# 00_POWER.net
KiCad netlist of a schematic drawn in Altium Designer
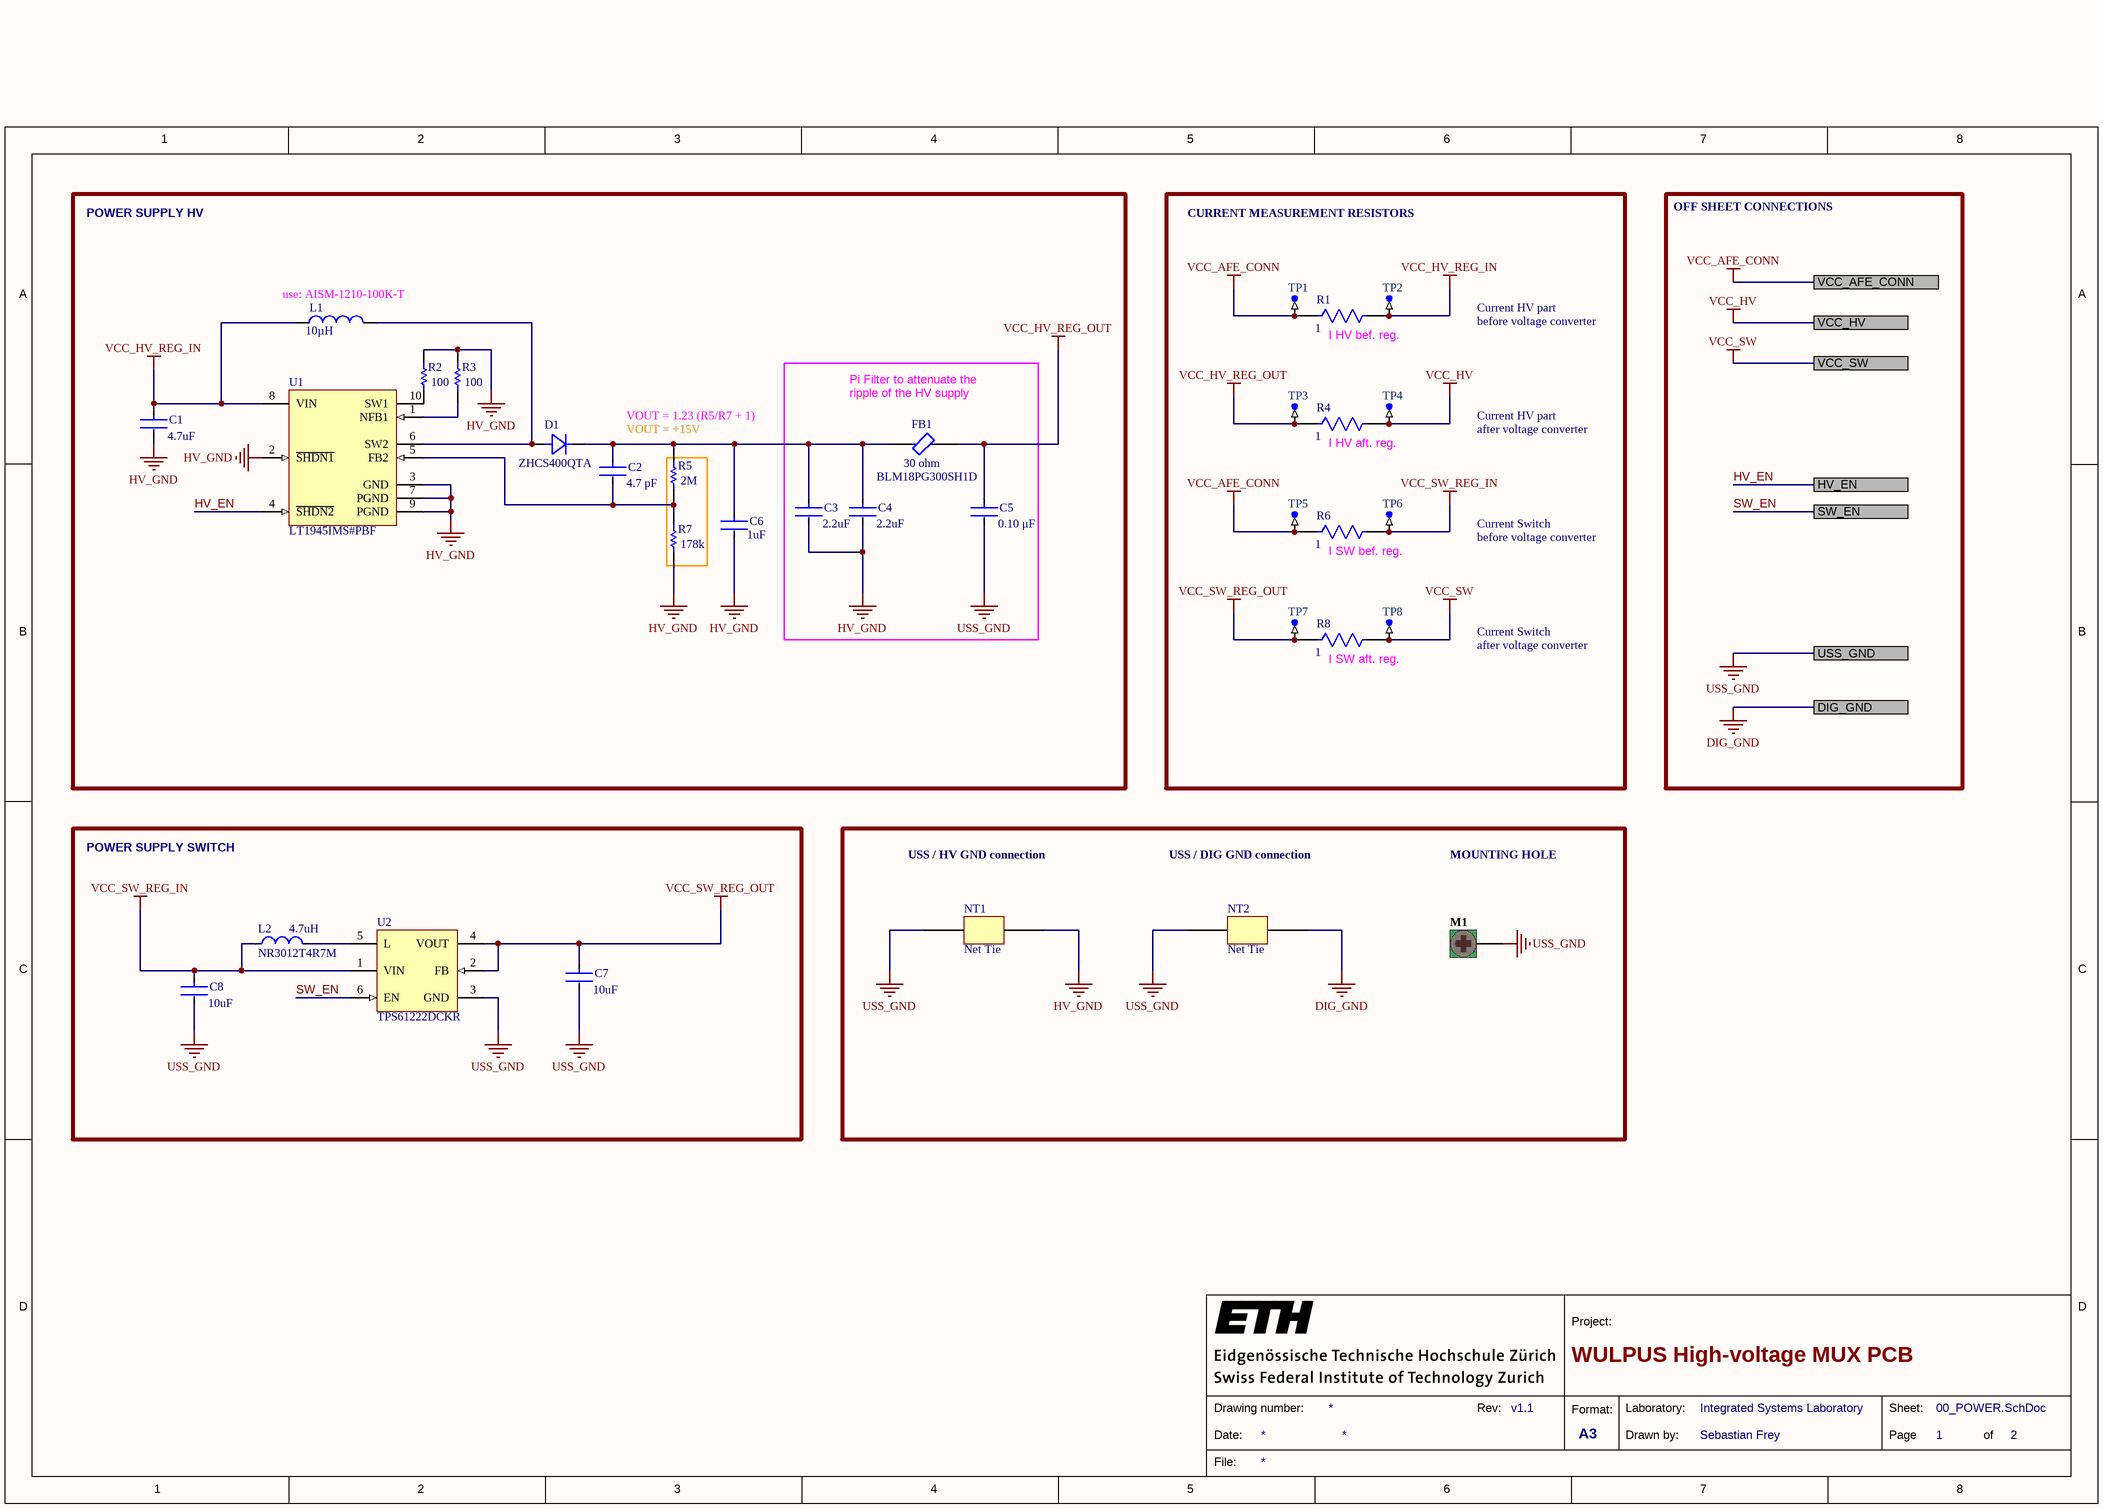
[diagram p0: 00_POWER.SchDoc]

(export (version "E")
  (design (tool "Eeschema 10.0.6"))
  (components
    (comp (ref "C1")
      (value "06036D475KAT2A")
      (footprint "FP-0603-L_1_6_0_15-W_0_81-MFG")
      (description "General Purpose Ceramic Capacitor, 0603, 4.7uF, 10%, X5R, 15%, 6.3V")
      (fields
        (field (name "VOLTAGE") "6.3V")
        (field (name "TOLERANCE") "20%")
        (field (name "CAPACITANCE") "4.7uF")
      )
      (libsource (lib "Altium Content Vault") (part "02cd4be3c70576c341d710602a673aa"))
    )
    (comp (ref "C2")
      (value "C0402C479C5GACTU")
      (footprint "FP-C0402-BB-MFG")
      (description "CAP CER 4.7PF 50V NP0 0402")
      (fields
        (field (name "TOLERANCE") "0.25 pF")
        (field (name "OCTOPART") "https://octopart.com/c0402c479c5gactu-kemet-9144199")
        (field (name "CAPACITANCE") "4.7 pF")
      )
      (libsource (lib "Altium Content Vault") (part "b4654b650e69147ec39a6b967a45e02"))
    )
    (comp (ref "C3")
      (value "GRM188R61H225KE11D")
      (footprint "FP-GRM188-0_2-IPC_C")
      (description "Chip Multilayer Ceramic Capacitors for General Purpose, 0603, 2.2uF, X5R, 15%, 10%, 50V")
      (fields (field (name "TOLERANCE") "10%") (field (name "CAPACITANCE") "2.2uF"))
      (libsource (lib "Altium Content Vault") (part "11868f565c42a9108669ba33697ecf6"))
    )
    (comp (ref "C4")
      (value "GRM188R61H225KE11D")
      (footprint "FP-GRM188-0_2-IPC_C")
      (description "Chip Multilayer Ceramic Capacitors for General Purpose, 0603, 2.2uF, X5R, 15%, 10%, 50V")
      (fields (field (name "TOLERANCE") "10%") (field (name "CAPACITANCE") "2.2uF"))
      (libsource (lib "Altium Content Vault") (part "11868f565c42a9108669ba33697ecf6"))
    )
    (comp (ref "C5")
      (value "0.10 μF")
      (footprint "FP-C0603C-CF-MFG")
      (description "CAP CER 0.1UF 50V 20% X7R 0603")
      (fields
        (field (name "MANUFACTURER PART NUMBER") "C0603C104M5RACTU")
        (field (name "MANUFACTURER") "KEMET")
      )
      (libsource (lib "Altium Content Vault") (part "b4654b650e69147ec39a6b967a45e02"))
    )
    (comp (ref "C6")
      (value "GMK316BJ105KLHT")
      (footprint "FP-1206-L_3_2_0_15-W_1_6-IPC_B")
      (description "None")
      (fields (field (name "CAPACITANCE") "1uF") (field (name "TOLERANCE") "10%"))
      (libsource (lib "Altium Content Vault") (part "02cd4be3c70576c341d710602a673aa"))
    )
    (comp (ref "C7")
      (value "GRM188R60J106ME47D")
      (footprint "FP-GRM188-0_1-e0_2_0_55-IPC_A")
      (description "Chip Multilayer Ceramic Capacitors for General Purpose, 0603, 10uF, X5R, 15%, 20%, 6.3V")
      (fields
        (field (name "CAPACITANCE") "10uF")
        (field (name "VOLTAGE") "6.3V")
        (field (name "TOLERANCE") "20%")
      )
      (libsource (lib "Altium Content Vault") (part "02cd4be3c70576c341d710602a673aa"))
    )
    (comp (ref "C8")
      (value "GRM188R60J106ME47D")
      (footprint "FP-GRM188-0_1-e0_2_0_55-IPC_A")
      (description "Chip Multilayer Ceramic Capacitors for General Purpose, 0603, 10uF, X5R, 15%, 20%, 6.3V")
      (fields
        (field (name "CAPACITANCE") "10uF")
        (field (name "VOLTAGE") "6.3V")
        (field (name "TOLERANCE") "20%")
      )
      (libsource (lib "Altium Content Vault") (part "02cd4be3c70576c341d710602a673aa"))
    )
    (comp (ref "D1")
      (value "ZHCS400QTA")
      (footprint "PcbLib1:DIODE_SOD323_DIO")
      (description "Diode Schottky 40V 1A Automotive 2-Pin SOD-323 T/R")
      (fields (field (name "MANUFACTURER") "Diodes"))
      (libsource (lib "Schlib1") (part "ZHCS400QTA"))
    )
    (comp (ref "FB1")
      (value "BLM18PG300SH1D")
      (footprint "FP-BLM18-0_15-t0_8-IPC_A")
      (description "Chip Ferrite Bead, 0603, 30Ω @ 100MHz, 0.05Ω, , 1A")
      (fields (field (name "IMPEDANCE") "30 ohm") (field (name "TOLERANCE") "25%"))
      (libsource (lib "Altium Content Vault") (part "5f30dd21d616792df468990f7003faa"))
    )
    (comp (ref "L1")
      (value "B82422A1103K100")
      (footprint "TDK-B82422A1103K100_V")
      (description "Wirewound Inductor, 10 uF, +/- 10%, 180 mA, -55 to 125 degC, 2-Pin SMD, RoHS, Tape and Reel")
      (fields
        (field (name "INDUCTANCE") "10µH")
        (field (name "TOLERANCE") "±10%")
        (field (name "MANUFACTURER") "EPCOS-(TDK)")
      )
      (libsource (lib "Altium Content Vault") (part "IND-2"))
    )
    (comp (ref "L2")
      (value "NR3012T4R7M")
      (footprint "FP-NR3012-MFG")
      (description "SMD Power Inductors 4.7uH ±20% 0.77A 0.13Ω")
      (fields (field (name "TOLERANCE") "20%") (field (name "INDUCTANCE") "4.7uH"))
      (libsource (lib "Altium Content Vault") (part "725321dda6339637d4d059423bc1c3c"))
    )
    (comp (ref "M1")
      (value "Mounting Hole for AFE PCB")
      (footprint "Hole M2")
      (description "M2 Hole, 2.4mm drill, 5mm landing pads, 3mm pad in middle layers, no overlay")
      (libsource (lib "ETHZ Vault") (part "Hole"))
    )
    (comp (ref "NT1")
      (value "Net Tie")
      (footprint "PcbLib1:Net_Tie_Top_Bottom")
      (libsource (lib "Schlib1") (part "Net_Tie"))
    )
    (comp (ref "NT2")
      (value "Net Tie")
      (footprint "PcbLib1:Net_Tie_Top_Bottom")
      (libsource (lib "Schlib1") (part "Net_Tie"))
    )
    (comp (ref "R1")
      (value "CSR0402FK1R00")
      (footprint "FP-CSR0402-MFG")
      (description "RES 1 OHM 1% 1/8W 0402")
      (fields (field (name "TOLERANCE") "1%") (field (name "RESISTANCE") "1"))
      (libsource (lib "Altium Content Vault") (part "1029c3af85768c4190bb7ad29bc67b5"))
    )
    (comp (ref "R2")
      (value "ERJ-2GEJ101X")
      (footprint "RESC1005X40X25NL05T05")
      (fields (field (name "MANUFACTURER") "Panasonic") (field (name "RESISTANCE") "100"))
      (libsource (lib "Altium Content Vault") (part "RES"))
    )
    (comp (ref "R3")
      (value "ERJ-2GEJ101X")
      (footprint "RESC1005X40X25NL05T05")
      (fields (field (name "MANUFACTURER") "Panasonic") (field (name "RESISTANCE") "100"))
      (libsource (lib "Altium Content Vault") (part "RES"))
    )
    (comp (ref "R4")
      (value "CSR0402FK1R00")
      (footprint "FP-CSR0402-MFG")
      (description "RES 1 OHM 1% 1/8W 0402")
      (fields (field (name "TOLERANCE") "1%") (field (name "RESISTANCE") "1"))
      (libsource (lib "Altium Content Vault") (part "1029c3af85768c4190bb7ad29bc67b5"))
    )
    (comp (ref "R5")
      (value "RC0402FR-072ML")
      (footprint "RESC1005X40X25NL05T10")
      (fields (field (name "MANUFACTURER") "Yageo / Phycomp") (field (name "RESISTANCE") "2M"))
      (libsource (lib "Altium Content Vault") (part "RES"))
    )
    (comp (ref "R6")
      (value "CSR0402FK1R00")
      (footprint "FP-CSR0402-MFG")
      (description "RES 1 OHM 1% 1/8W 0402")
      (fields (field (name "TOLERANCE") "1%") (field (name "RESISTANCE") "1"))
      (libsource (lib "Altium Content Vault") (part "1029c3af85768c4190bb7ad29bc67b5"))
    )
    (comp (ref "R7")
      (value "ERJ-2RKF1783X")
      (footprint "RESC1005X40X25ML05T05")
      (fields (field (name "MANUFACTURER") "Panasonic") (field (name "RESISTANCE") "178k"))
      (libsource (lib "Altium Content Vault") (part "RES"))
    )
    (comp (ref "R8")
      (value "CSR0402FK1R00")
      (footprint "FP-CSR0402-MFG")
      (description "RES 1 OHM 1% 1/8W 0402")
      (fields (field (name "TOLERANCE") "1%") (field (name "RESISTANCE") "1"))
      (libsource (lib "Altium Content Vault") (part "1029c3af85768c4190bb7ad29bc67b5"))
    )
    (comp (ref "TP1")
      (value "TP-SM-C-100")
      (footprint "TP-SM-C-100")
      (description "Test Point, Surface Mount, Circular, Pad Diameter 1 mm")
      (libsource (lib "Altium Content Vault") (part "TP-SM"))
    )
    (comp (ref "TP2")
      (value "TP-SM-C-100")
      (footprint "TP-SM-C-100")
      (description "Test Point, Surface Mount, Circular, Pad Diameter 1 mm")
      (libsource (lib "Altium Content Vault") (part "TP-SM"))
    )
    (comp (ref "TP3")
      (value "TP-SM-C-100")
      (footprint "TP-SM-C-100")
      (description "Test Point, Surface Mount, Circular, Pad Diameter 1 mm")
      (libsource (lib "Altium Content Vault") (part "TP-SM"))
    )
    (comp (ref "TP4")
      (value "TP-SM-C-100")
      (footprint "TP-SM-C-100")
      (description "Test Point, Surface Mount, Circular, Pad Diameter 1 mm")
      (libsource (lib "Altium Content Vault") (part "TP-SM"))
    )
    (comp (ref "TP5")
      (value "TP-SM-C-100")
      (footprint "TP-SM-C-100")
      (description "Test Point, Surface Mount, Circular, Pad Diameter 1 mm")
      (libsource (lib "Altium Content Vault") (part "TP-SM"))
    )
    (comp (ref "TP6")
      (value "TP-SM-C-100")
      (footprint "TP-SM-C-100")
      (description "Test Point, Surface Mount, Circular, Pad Diameter 1 mm")
      (libsource (lib "Altium Content Vault") (part "TP-SM"))
    )
    (comp (ref "TP7")
      (value "TP-SM-C-100")
      (footprint "TP-SM-C-100")
      (description "Test Point, Surface Mount, Circular, Pad Diameter 1 mm")
      (libsource (lib "Altium Content Vault") (part "TP-SM"))
    )
    (comp (ref "TP8")
      (value "TP-SM-C-100")
      (footprint "TP-SM-C-100")
      (description "Test Point, Surface Mount, Circular, Pad Diameter 1 mm")
      (libsource (lib "Altium Content Vault") (part "TP-SM"))
    )
    (comp (ref "U1")
      (value "LT1945IMS#PBF")
      (footprint "LT-MS-10_L")
      (fields (field (name "MANUFACTURER") "Linear Technology"))
      (libsource (lib "Altium Content Vault") (part "LT-LT1945-MS-10"))
    )
    (comp (ref "U2")
      (value "TPS61222DCKR")
      (footprint "DCK0006A_L")
      (fields (field (name "MANUFACTURER") "Texas Instruments"))
      (libsource (lib "Altium Content Vault") (part "TI-TPS61222DCK6"))
    )
  )
  (nets
    (net (code "1") (name "/HV_EN") (class "Default")
      (node (ref "U1") (pin "4") (pinfunction "~{SHDN2}_4") (pintype "input"))
    )
    (net (code "2") (name "/SW_EN") (class "Default")
      (node (ref "U2") (pin "6") (pinfunction "EN_6") (pintype "input"))
    )
    (net (code "3") (name "DIG_GND") (class "Default")
      (node (ref "NT2") (pin "2") (pinfunction "2_2") (pintype "passive"))
    )
    (net (code "4") (name "HV_GND") (class "Default")
      (node (ref "C1") (pin "2") (pinfunction "2_2") (pintype "passive"))
      (node (ref "C3") (pin "2") (pinfunction "2_2") (pintype "passive"))
      (node (ref "C4") (pin "2") (pinfunction "2_2") (pintype "passive"))
      (node (ref "C6") (pin "2") (pinfunction "2_2") (pintype "passive"))
      (node (ref "NT1") (pin "2") (pinfunction "2_2") (pintype "passive"))
      (node (ref "R2") (pin "2") (pinfunction "2_2") (pintype "passive"))
      (node (ref "R3") (pin "2") (pinfunction "2_2") (pintype "passive"))
      (node (ref "R7") (pin "1") (pinfunction "1_1") (pintype "passive"))
      (node (ref "U1") (pin "2") (pinfunction "~{SHDN1}_2") (pintype "input"))
      (node (ref "U1") (pin "3") (pinfunction "GND_3") (pintype "power_in"))
      (node (ref "U1") (pin "7") (pinfunction "PGND_7") (pintype "power_in"))
      (node (ref "U1") (pin "9") (pinfunction "PGND_9") (pintype "power_in"))
    )
    (net (code "5") (name "Net-(C2-Pad1)") (class "Default")
      (node (ref "C2") (pin "1") (pinfunction "1_1") (pintype "passive"))
      (node (ref "C3") (pin "1") (pinfunction "1_1") (pintype "passive"))
      (node (ref "C4") (pin "1") (pinfunction "1_1") (pintype "passive"))
      (node (ref "C6") (pin "1") (pinfunction "1_1") (pintype "passive"))
      (node (ref "D1") (pin "1") (pinfunction "1_1") (pintype "passive"))
      (node (ref "FB1") (pin "1") (pinfunction "1_1") (pintype "passive"))
      (node (ref "R5") (pin "2") (pinfunction "2_2") (pintype "passive"))
    )
    (net (code "6") (name "Net-(U1-FB2)") (class "Default")
      (node (ref "C2") (pin "2") (pinfunction "2_2") (pintype "passive"))
      (node (ref "R5") (pin "1") (pinfunction "1_1") (pintype "passive"))
      (node (ref "R7") (pin "2") (pinfunction "2_2") (pintype "passive"))
      (node (ref "U1") (pin "5") (pinfunction "FB2_5") (pintype "input"))
    )
    (net (code "7") (name "Net-(U1-NFB1)") (class "Default")
      (node (ref "R3") (pin "1") (pinfunction "1_1") (pintype "passive"))
      (node (ref "U1") (pin "1") (pinfunction "NFB1_1") (pintype "input"))
    )
    (net (code "8") (name "Net-(U1-SW1)") (class "Default")
      (node (ref "R2") (pin "1") (pinfunction "1_1") (pintype "passive"))
      (node (ref "U1") (pin "10") (pinfunction "SW1_10") (pintype "power_in"))
    )
    (net (code "9") (name "Net-(U1-SW2)") (class "Default")
      (node (ref "D1") (pin "2") (pinfunction "2_2") (pintype "passive"))
      (node (ref "L1") (pin "2") (pinfunction "2_2") (pintype "passive"))
      (node (ref "U1") (pin "6") (pinfunction "SW2_6") (pintype "power_in"))
    )
    (net (code "10") (name "Net-(U2-L)") (class "Default")
      (node (ref "L2") (pin "2") (pinfunction "2_2") (pintype "passive"))
      (node (ref "U2") (pin "5") (pinfunction "L_5") (pintype "power_in"))
    )
    (net (code "11") (name "USS_GND") (class "Default")
      (node (ref "C5") (pin "2") (pinfunction "2_2") (pintype "passive"))
      (node (ref "C7") (pin "2") (pinfunction "2_2") (pintype "passive"))
      (node (ref "C8") (pin "2") (pinfunction "2_2") (pintype "passive"))
      (node (ref "M1") (pin "1") (pinfunction "1_1") (pintype "passive"))
      (node (ref "NT1") (pin "1") (pinfunction "1_1") (pintype "passive"))
      (node (ref "NT2") (pin "1") (pinfunction "1_1") (pintype "passive"))
      (node (ref "U2") (pin "3") (pinfunction "GND_3") (pintype "power_in"))
    )
    (net (code "12") (name "VCC_AFE_CONN") (class "Default")
      (node (ref "R1") (pin "1") (pinfunction "1_1") (pintype "passive"))
      (node (ref "R6") (pin "1") (pinfunction "1_1") (pintype "passive"))
      (node (ref "TP1") (pin "1") (pinfunction "1_1") (pintype "input"))
      (node (ref "TP5") (pin "1") (pinfunction "1_1") (pintype "input"))
    )
    (net (code "13") (name "VCC_HV") (class "Default")
      (node (ref "R4") (pin "2") (pinfunction "2_2") (pintype "passive"))
      (node (ref "TP4") (pin "1") (pinfunction "1_1") (pintype "input"))
    )
    (net (code "14") (name "VCC_HV_REG_IN") (class "Default")
      (node (ref "C1") (pin "1") (pinfunction "1_1") (pintype "passive"))
      (node (ref "L1") (pin "1") (pinfunction "1_1") (pintype "passive"))
      (node (ref "R1") (pin "2") (pinfunction "2_2") (pintype "passive"))
      (node (ref "TP2") (pin "1") (pinfunction "1_1") (pintype "input"))
      (node (ref "U1") (pin "8") (pinfunction "VIN_8") (pintype "power_in"))
    )
    (net (code "15") (name "VCC_HV_REG_OUT") (class "Default")
      (node (ref "C5") (pin "1") (pinfunction "1_1") (pintype "passive"))
      (node (ref "FB1") (pin "2") (pinfunction "2_2") (pintype "passive"))
      (node (ref "R4") (pin "1") (pinfunction "1_1") (pintype "passive"))
      (node (ref "TP3") (pin "1") (pinfunction "1_1") (pintype "input"))
    )
    (net (code "16") (name "VCC_SW") (class "Default")
      (node (ref "R8") (pin "2") (pinfunction "2_2") (pintype "passive"))
      (node (ref "TP8") (pin "1") (pinfunction "1_1") (pintype "input"))
    )
    (net (code "17") (name "VCC_SW_REG_IN") (class "Default")
      (node (ref "C8") (pin "1") (pinfunction "1_1") (pintype "passive"))
      (node (ref "L2") (pin "1") (pinfunction "1_1") (pintype "passive"))
      (node (ref "R6") (pin "2") (pinfunction "2_2") (pintype "passive"))
      (node (ref "TP6") (pin "1") (pinfunction "1_1") (pintype "input"))
      (node (ref "U2") (pin "1") (pinfunction "VIN_1") (pintype "power_in"))
    )
    (net (code "18") (name "VCC_SW_REG_OUT") (class "Default")
      (node (ref "C7") (pin "1") (pinfunction "1_1") (pintype "passive"))
      (node (ref "R8") (pin "1") (pinfunction "1_1") (pintype "passive"))
      (node (ref "TP7") (pin "1") (pinfunction "1_1") (pintype "input"))
      (node (ref "U2") (pin "2") (pinfunction "FB_2") (pintype "input"))
      (node (ref "U2") (pin "4") (pinfunction "VOUT_4") (pintype "power_in"))
    )
  )
)
